# EVAL_51296.net
KiCad netlist of a schematic drawn in EAGLE
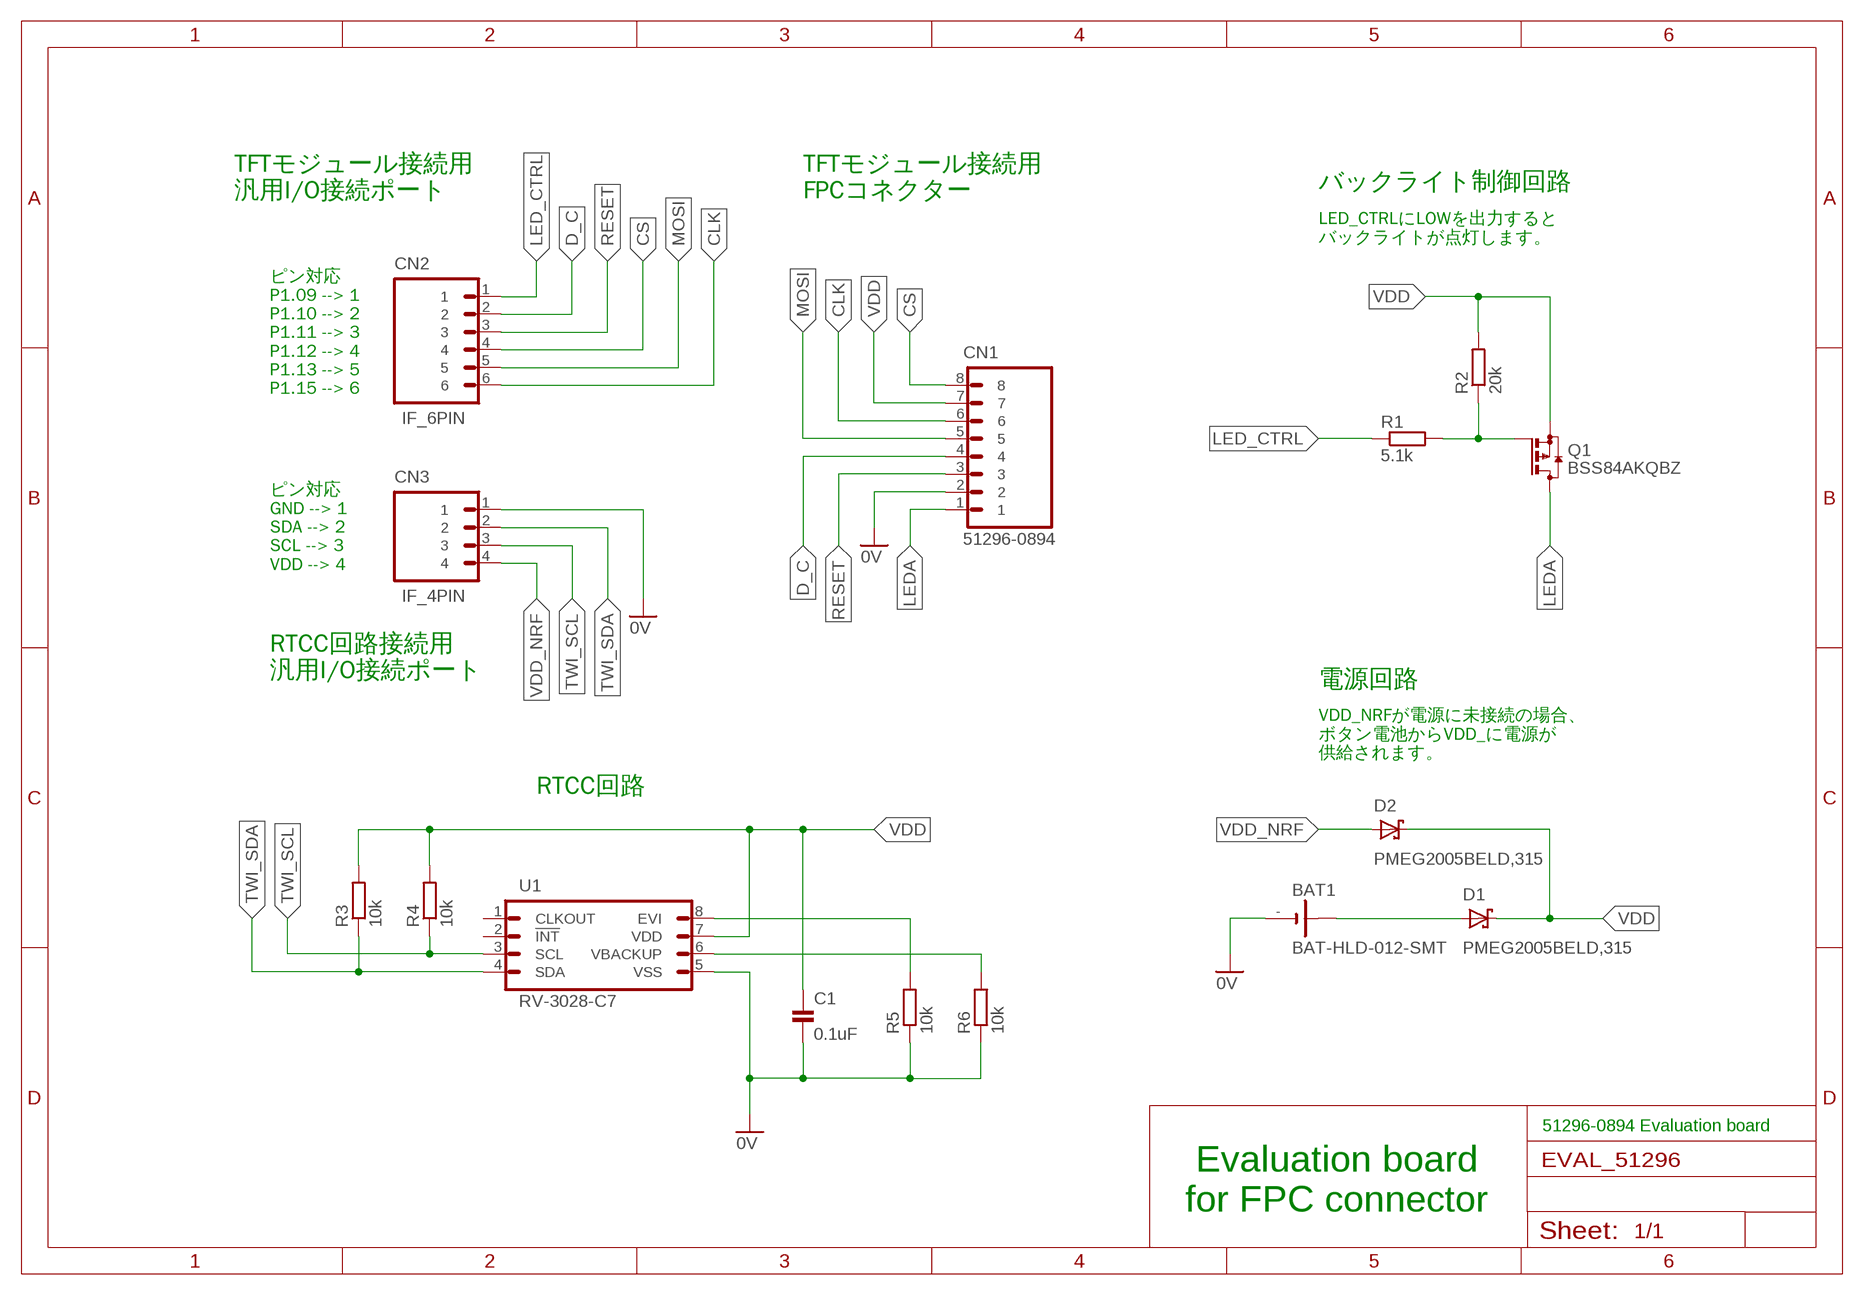
[diagram p0: schematic, sheet 1]

(export (version "E")
  (design (tool "Eeschema 10.0.6"))
  (components
    (comp (ref "BAT1")
      (value "BAT-HLD-012-SMT")
      (footprint "eagle-import:BAT-HLD-012-SMT")
      (libsource (lib "eagle-import") (part "BAT-HLD-012-SMT"))
    )
    (comp (ref "C1")
      (value "0.1uF")
      (footprint "eagle-import:C0402N")
      (libsource (lib "eagle-import") (part "CAP_0402N"))
    )
    (comp (ref "CN1")
      (value "51296-0894")
      (footprint "eagle-import:51296-0894")
      (libsource (lib "eagle-import") (part "51296-0894"))
    )
    (comp (ref "CN2")
      (value "IF_6PIN")
      (footprint "eagle-import:HEADER_6PIN")
      (libsource (lib "eagle-import") (part "IF_6PIN"))
    )
    (comp (ref "CN3")
      (value "IF_4PIN")
      (footprint "eagle-import:HEADER_4PIN")
      (libsource (lib "eagle-import") (part "IF_4PIN"))
    )
    (comp (ref "D1")
      (value "PMEG2005BELD,315")
      (footprint "eagle-import:DFN1006D-2")
      (libsource (lib "eagle-import") (part "PMEG2005BELD,315"))
    )
    (comp (ref "D2")
      (value "PMEG2005BELD,315")
      (footprint "eagle-import:DFN1006D-2")
      (libsource (lib "eagle-import") (part "PMEG2005BELD,315"))
    )
    (comp (ref "Q1")
      (value "BSS84AKQBZ")
      (footprint "eagle-import:BSS84AKQB")
      (libsource (lib "eagle-import") (part "BSS84AKQBZ"))
    )
    (comp (ref "R1")
      (value "5.1k")
      (footprint "eagle-import:R0402N")
      (libsource (lib "eagle-import") (part "RESISTOR_0402N"))
    )
    (comp (ref "R2")
      (value "20k")
      (footprint "eagle-import:R0402N")
      (libsource (lib "eagle-import") (part "RESISTOR_0402N"))
    )
    (comp (ref "R3")
      (value "10k")
      (footprint "eagle-import:R0402N")
      (libsource (lib "eagle-import") (part "RESISTOR_0402N"))
    )
    (comp (ref "R4")
      (value "10k")
      (footprint "eagle-import:R0402N")
      (libsource (lib "eagle-import") (part "RESISTOR_0402N"))
    )
    (comp (ref "R5")
      (value "10k")
      (footprint "eagle-import:R0402N")
      (libsource (lib "eagle-import") (part "RESISTOR_0402N"))
    )
    (comp (ref "R6")
      (value "10k")
      (footprint "eagle-import:R0402N")
      (libsource (lib "eagle-import") (part "RESISTOR_0402N"))
    )
    (comp (ref "U1")
      (value "RV-3028-C7")
      (footprint "eagle-import:SON-8")
      (libsource (lib "eagle-import") (part "RV-3028-C7"))
    )
  )
  (nets
    (net (code "1") (name "0V") (class "Default")
      (node (ref "BAT1") (pin "-") (pinfunction "-_-") (pintype "passive"))
      (node (ref "C1") (pin "2") (pinfunction "2_2") (pintype "passive"))
      (node (ref "CN1") (pin "2") (pinfunction "2_2") (pintype "passive"))
      (node (ref "CN3") (pin "1") (pinfunction "1_1") (pintype "passive"))
      (node (ref "R5") (pin "1") (pinfunction "1_1") (pintype "passive"))
      (node (ref "R6") (pin "1") (pinfunction "1_1") (pintype "passive"))
      (node (ref "U1") (pin "5") (pinfunction "VSS_5") (pintype "passive"))
    )
    (net (code "2") (name "CLK") (class "Default")
      (node (ref "CN1") (pin "6") (pinfunction "6_6") (pintype "passive"))
      (node (ref "CN2") (pin "6") (pinfunction "6_6") (pintype "passive"))
    )
    (net (code "3") (name "CS") (class "Default")
      (node (ref "CN1") (pin "8") (pinfunction "8_8") (pintype "passive"))
      (node (ref "CN2") (pin "4") (pinfunction "4_4") (pintype "passive"))
    )
    (net (code "4") (name "D_C") (class "Default")
      (node (ref "CN1") (pin "4") (pinfunction "4_4") (pintype "passive"))
      (node (ref "CN2") (pin "2") (pinfunction "2_2") (pintype "passive"))
    )
    (net (code "5") (name "LEDA") (class "Default")
      (node (ref "CN1") (pin "1") (pinfunction "1_1") (pintype "passive"))
      (node (ref "Q1") (pin "3") (pinfunction "D_3") (pintype "passive"))
    )
    (net (code "6") (name "LED_CTRL") (class "Default")
      (node (ref "CN2") (pin "1") (pinfunction "1_1") (pintype "passive"))
      (node (ref "R1") (pin "1") (pinfunction "1_1") (pintype "passive"))
    )
    (net (code "7") (name "MOSI") (class "Default")
      (node (ref "CN1") (pin "5") (pinfunction "5_5") (pintype "passive"))
      (node (ref "CN2") (pin "5") (pinfunction "5_5") (pintype "passive"))
    )
    (net (code "8") (name "Net-(BAT1-+)") (class "Default")
      (node (ref "BAT1") (pin "+@2") (pinfunction "+_+@2") (pintype "passive"))
      (node (ref "D1") (pin "2") (pinfunction "A_2") (pintype "passive"))
    )
    (net (code "9") (name "Net-(Q1-G)") (class "Default")
      (node (ref "Q1") (pin "1") (pinfunction "G_1") (pintype "passive"))
      (node (ref "R1") (pin "2") (pinfunction "2_2") (pintype "passive"))
      (node (ref "R2") (pin "1") (pinfunction "1_1") (pintype "passive"))
    )
    (net (code "10") (name "Net-(U1-EVI)") (class "Default")
      (node (ref "R5") (pin "2") (pinfunction "2_2") (pintype "passive"))
      (node (ref "U1") (pin "8") (pinfunction "EVI_8") (pintype "bidirectional"))
    )
    (net (code "11") (name "Net-(U1-VBACKUP)") (class "Default")
      (node (ref "R6") (pin "2") (pinfunction "2_2") (pintype "passive"))
      (node (ref "U1") (pin "6") (pinfunction "VBACKUP_6") (pintype "passive"))
    )
    (net (code "12") (name "RESET") (class "Default")
      (node (ref "CN1") (pin "3") (pinfunction "3_3") (pintype "passive"))
      (node (ref "CN2") (pin "3") (pinfunction "3_3") (pintype "passive"))
    )
    (net (code "13") (name "TWI_SCL") (class "Default")
      (node (ref "CN3") (pin "3") (pinfunction "3_3") (pintype "passive"))
      (node (ref "R4") (pin "1") (pinfunction "1_1") (pintype "passive"))
      (node (ref "U1") (pin "3") (pinfunction "SCL_3") (pintype "bidirectional"))
    )
    (net (code "14") (name "TWI_SDA") (class "Default")
      (node (ref "CN3") (pin "2") (pinfunction "2_2") (pintype "passive"))
      (node (ref "R3") (pin "1") (pinfunction "1_1") (pintype "passive"))
      (node (ref "U1") (pin "4") (pinfunction "SDA_4") (pintype "bidirectional"))
    )
    (net (code "15") (name "VDD") (class "Default")
      (node (ref "C1") (pin "1") (pinfunction "1_1") (pintype "passive"))
      (node (ref "CN1") (pin "7") (pinfunction "7_7") (pintype "passive"))
      (node (ref "D1") (pin "1") (pinfunction "C_1") (pintype "passive"))
      (node (ref "D2") (pin "1") (pinfunction "C_1") (pintype "passive"))
      (node (ref "Q1") (pin "2") (pinfunction "S_2") (pintype "passive"))
      (node (ref "R2") (pin "2") (pinfunction "2_2") (pintype "passive"))
      (node (ref "R3") (pin "2") (pinfunction "2_2") (pintype "passive"))
      (node (ref "R4") (pin "2") (pinfunction "2_2") (pintype "passive"))
      (node (ref "U1") (pin "7") (pinfunction "VDD_7") (pintype "passive"))
    )
    (net (code "16") (name "VDD_NRF") (class "Default")
      (node (ref "CN3") (pin "4") (pinfunction "4_4") (pintype "passive"))
      (node (ref "D2") (pin "2") (pinfunction "A_2") (pintype "passive"))
    )
    (net (code "17") (name "unconnected-(U1-CLKOUT-Pad1)") (class "Default")
      (node (ref "U1") (pin "1") (pinfunction "CLKOUT_1") (pintype "bidirectional"))
    )
    (net (code "18") (name "unconnected-(U1-~{INT}-Pad2)") (class "Default")
      (node (ref "U1") (pin "2") (pinfunction "~{INT}_2") (pintype "bidirectional"))
    )
  )
)
